# schema_Project.net
KiCad netlist of a schematic drawn in Altium Designer
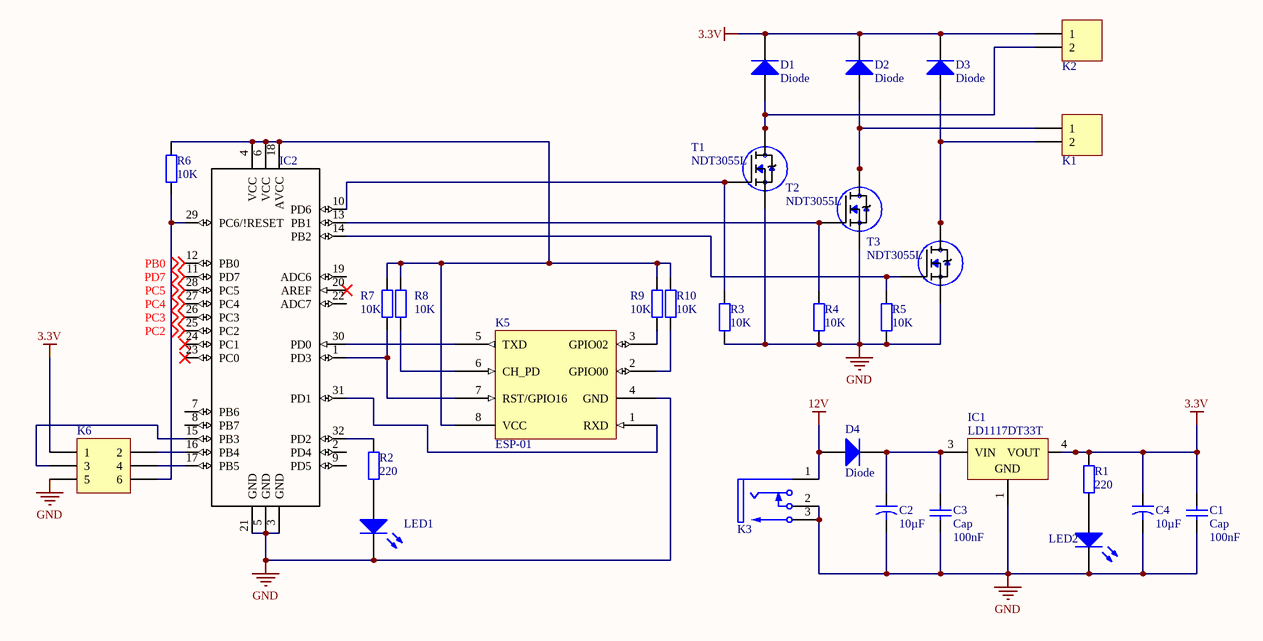
[diagram p0: schema_Project.SchDoc]

(export (version "E")
  (design (tool "Eeschema 10.0.6"))
  (components
    (comp (ref "C1")
      (value "Cap")
      (footprint "C13+R")
      (description "Capacitor")
      (fields (field (name "ALTIUM_VALUE") "100nF") (field (name "PUBLISHER") "Altium Limited"))
      (libsource (lib "Miscellaneous Devices") (part "Cap"))
    )
    (comp (ref "C2")
      (value "10µF")
      (footprint "C24")
      (description "Capacitor")
      (fields (field (name "Comment") "Cap2") (field (name "PUBLISHER") "Altium Limited"))
      (libsource (lib "Miscellaneous Devices") (part "Cap2"))
    )
    (comp (ref "C3")
      (value "Cap")
      (footprint "C13+R")
      (description "Capacitor")
      (fields (field (name "ALTIUM_VALUE") "100nF") (field (name "PUBLISHER") "Altium Limited"))
      (libsource (lib "Miscellaneous Devices") (part "Cap"))
    )
    (comp (ref "C4")
      (value "10µF")
      (footprint "C24")
      (description "Capacitor")
      (fields (field (name "Comment") "Cap2") (field (name "PUBLISHER") "Altium Limited"))
      (libsource (lib "Miscellaneous Devices") (part "Cap2"))
    )
    (comp (ref "D1")
      (value "Diode")
      (footprint "Diode")
      (description "Default Diode")
      (fields (field (name "PUBLISHER") "Altium Limited"))
      (libsource (lib "Miscellaneous Devices") (part "Diode"))
    )
    (comp (ref "D2")
      (value "Diode")
      (footprint "Diode")
      (description "Default Diode")
      (fields (field (name "PUBLISHER") "Altium Limited"))
      (libsource (lib "Miscellaneous Devices") (part "Diode"))
    )
    (comp (ref "D3")
      (value "Diode")
      (footprint "Diode")
      (description "Default Diode")
      (fields (field (name "PUBLISHER") "Altium Limited"))
      (libsource (lib "Miscellaneous Devices") (part "Diode"))
    )
    (comp (ref "D4")
      (value "Diode")
      (footprint "Diode")
      (description "Default Diode")
      (fields (field (name "PUBLISHER") "Altium Limited"))
      (libsource (lib "Miscellaneous Devices") (part "Diode"))
    )
    (comp (ref "ESP-01") (value "K5") (footprint "HDR2X4") (libsource (lib "ESP-01") (part "K5")))
    (comp (ref "IC1")
      (value "LD1117DT33T")
      (footprint "TO-252_N")
      (description "Fixed Low Drop Positive Voltage Regulator, 3.3V, 3-Pin DPAK, Tape and Reel")
      (libsource (lib "Altium Content Vault") (part "PM-REG-LD1117-SOT3"))
    )
    (comp (ref "IC2")
      (value "ATMEGA328P-AU")
      (footprint "*QFP80P900X900X120-32N")
      (libsource (lib "AT-MEGA") (part "Component_1"))
    )
    (comp (ref "K1")
      (value "K1")
      (footprint "K12")
      (description "Header, 2-Pin")
      (fields (field (name "PUBLISHER") "Altium Limited"))
      (libsource (lib "Miscellaneous Connectors") (part "Header 2"))
    )
    (comp (ref "K2")
      (value "K2")
      (footprint "K12")
      (description "Header, 2-Pin")
      (fields (field (name "PUBLISHER") "Altium Limited"))
      (libsource (lib "Miscellaneous Connectors") (part "Header 2"))
    )
    (comp (ref "K3")
      (value "K3")
      (footprint "SWITCH-RAPC712X-3_V")
      (description "Power Jack, 5 A, 3-Pin THD, RoHS, Bulk")
      (fields (field (name "MANUFACTURER") "Switchcraft"))
      (libsource (lib "Altium Content Vault") (part "SWITCH-RAPC712X-3"))
    )
    (comp (ref "K6")
      (value "Header 3X2")
      (footprint "HDR2X3")
      (description "Header, 3-Pin, Dual row")
      (fields (field (name "PUBLISHER") "Altium Limited"))
      (libsource (lib "Miscellaneous Connectors") (part "Header 3X2"))
    )
    (comp (ref "LED1")
      (value "LED1")
      (footprint "LED")
      (description "Typical RED GaAs LED")
      (fields (field (name "PUBLISHER") "Altium Limited"))
      (libsource (lib "Miscellaneous Devices") (part "LED1"))
    )
    (comp (ref "LED2")
      (value "LED2")
      (footprint "LED")
      (description "Typical RED, GREEN, YELLOW, AMBER GaAs LED")
      (fields (field (name "PUBLISHER") "Altium Limited"))
      (libsource (lib "Miscellaneous Devices") (part "LED2"))
    )
    (comp (ref "R1")
      (value "220")
      (footprint "C13+R")
      (description "Resistor")
      (fields (field (name "Comment") "Res2") (field (name "PUBLISHER") "Altium Limited"))
      (libsource (lib "Miscellaneous Devices") (part "Res2"))
    )
    (comp (ref "R2")
      (value "220")
      (footprint "C13+R")
      (description "Resistor")
      (fields (field (name "Comment") "Res2") (field (name "PUBLISHER") "Altium Limited"))
      (libsource (lib "Miscellaneous Devices") (part "Res2"))
    )
    (comp (ref "R3")
      (value "10K")
      (footprint "C13+R")
      (description "Resistor")
      (fields (field (name "Comment") "Res2") (field (name "PUBLISHER") "Altium Limited"))
      (libsource (lib "") (part "Res2_1"))
    )
    (comp (ref "R4")
      (value "10K")
      (footprint "C13+R")
      (description "Resistor")
      (fields (field (name "Comment") "Res2") (field (name "PUBLISHER") "Altium Limited"))
      (libsource (lib "Miscellaneous Devices") (part "Res2"))
    )
    (comp (ref "R5")
      (value "10K")
      (footprint "C13+R")
      (description "Resistor")
      (fields (field (name "Comment") "Res2") (field (name "PUBLISHER") "Altium Limited"))
      (libsource (lib "Miscellaneous Devices") (part "Res2"))
    )
    (comp (ref "R6")
      (value "10K")
      (footprint "C13+R")
      (description "Resistor")
      (fields (field (name "Comment") "Res2") (field (name "PUBLISHER") "Altium Limited"))
      (libsource (lib "Miscellaneous Devices") (part "Res2"))
    )
    (comp (ref "R7")
      (value "10K")
      (footprint "C13+R")
      (description "Resistor")
      (fields (field (name "Comment") "Res2") (field (name "PUBLISHER") "Altium Limited"))
      (libsource (lib "") (part "Res2_1"))
    )
    (comp (ref "R8")
      (value "10K")
      (footprint "C13+R")
      (description "Resistor")
      (fields (field (name "Comment") "Res2") (field (name "PUBLISHER") "Altium Limited"))
      (libsource (lib "Miscellaneous Devices") (part "Res2"))
    )
    (comp (ref "R9")
      (value "10K")
      (footprint "C13+R")
      (description "Resistor")
      (fields (field (name "Comment") "Res2") (field (name "PUBLISHER") "Altium Limited"))
      (libsource (lib "Miscellaneous Devices") (part "Res2"))
    )
    (comp (ref "R10")
      (value "10K")
      (footprint "C13+R")
      (description "Resistor")
      (fields (field (name "Comment") "Res2") (field (name "PUBLISHER") "Altium Limited"))
      (libsource (lib "Miscellaneous Devices") (part "Res2"))
    )
    (comp (ref "T1")
      (value "NDT3055L")
      (footprint "*SOT223-4")
      (libsource (lib "NDT3055L") (part "NDT3055L"))
    )
    (comp (ref "T2")
      (value "NDT3055L")
      (footprint "*SOT223-4")
      (libsource (lib "NDT3055L") (part "NDT3055L"))
    )
    (comp (ref "T3")
      (value "NDT3055L")
      (footprint "*SOT223-4")
      (libsource (lib "NDT3055L") (part "NDT3055L"))
    )
  )
  (nets
    (net (code "1") (name "3.3V") (class "Default")
      (node (ref "C1") (pin "2") (pinfunction "2_2") (pintype "passive"))
      (node (ref "C4") (pin "1") (pinfunction "1_1") (pintype "passive"))
      (node (ref "D1") (pin "K") (pinfunction "K_K") (pintype "passive"))
      (node (ref "D2") (pin "K") (pinfunction "K_K") (pintype "passive"))
      (node (ref "D3") (pin "K") (pinfunction "K_K") (pintype "passive"))
      (node (ref "IC1") (pin "4") (pinfunction "VOUT_4") (pintype "power_in"))
      (node (ref "K2") (pin "1") (pinfunction "1_1") (pintype "passive"))
      (node (ref "K6") (pin "1") (pinfunction "1_1") (pintype "passive"))
      (node (ref "R1") (pin "2") (pinfunction "2_2") (pintype "passive"))
    )
    (net (code "2") (name "12V") (class "Default")
      (node (ref "D4") (pin "A") (pinfunction "A_A") (pintype "passive"))
      (node (ref "K3") (pin "1") (pinfunction "1_1") (pintype "passive"))
    )
    (net (code "3") (name "GND") (class "Default")
      (node (ref "C1") (pin "1") (pinfunction "1_1") (pintype "passive"))
      (node (ref "C2") (pin "2") (pinfunction "2_2") (pintype "passive"))
      (node (ref "C3") (pin "1") (pinfunction "1_1") (pintype "passive"))
      (node (ref "C4") (pin "2") (pinfunction "2_2") (pintype "passive"))
      (node (ref "ESP-01") (pin "4") (pinfunction "GND_4") (pintype "passive"))
      (node (ref "IC1") (pin "1") (pinfunction "GND_1") (pintype "power_in"))
      (node (ref "IC2") (pin "21") (pinfunction "GND_21") (pintype "power_in"))
      (node (ref "IC2") (pin "3") (pinfunction "GND_3") (pintype "power_in"))
      (node (ref "IC2") (pin "5") (pinfunction "GND_5") (pintype "power_in"))
      (node (ref "K3") (pin "2") (pinfunction "2_2") (pintype "passive"))
      (node (ref "K3") (pin "3") (pinfunction "3_3") (pintype "passive"))
      (node (ref "K6") (pin "5") (pinfunction "5_5") (pintype "passive"))
      (node (ref "LED1") (pin "K") (pinfunction "K_K") (pintype "passive"))
      (node (ref "LED2") (pin "K") (pinfunction "K_K") (pintype "passive"))
      (node (ref "R3") (pin "2") (pinfunction "2_2") (pintype "passive"))
      (node (ref "R4") (pin "1") (pinfunction "1_1") (pintype "passive"))
      (node (ref "R5") (pin "1") (pinfunction "1_1") (pintype "passive"))
      (node (ref "T1") (pin "3") (pinfunction "S_3") (pintype "passive"))
      (node (ref "T2") (pin "3") (pinfunction "S_3") (pintype "passive"))
      (node (ref "T3") (pin "3") (pinfunction "S_3") (pintype "passive"))
    )
    (net (code "4") (name "Net-(D1-PadA)") (class "Default")
      (node (ref "D1") (pin "A") (pinfunction "A_A") (pintype "passive"))
      (node (ref "K2") (pin "2") (pinfunction "2_2") (pintype "passive"))
      (node (ref "T1") (pin "2") (pinfunction "D_2") (pintype "passive"))
      (node (ref "T1") (pin "4") (pinfunction "D_4") (pintype "passive"))
    )
    (net (code "5") (name "Net-(D2-PadA)") (class "Default")
      (node (ref "D2") (pin "A") (pinfunction "A_A") (pintype "passive"))
      (node (ref "K1") (pin "1") (pinfunction "1_1") (pintype "passive"))
      (node (ref "T2") (pin "2") (pinfunction "D_2") (pintype "passive"))
      (node (ref "T2") (pin "4") (pinfunction "D_4") (pintype "passive"))
    )
    (net (code "6") (name "Net-(D3-PadA)") (class "Default")
      (node (ref "D3") (pin "A") (pinfunction "A_A") (pintype "passive"))
      (node (ref "K1") (pin "2") (pinfunction "2_2") (pintype "passive"))
      (node (ref "T3") (pin "2") (pinfunction "D_2") (pintype "passive"))
      (node (ref "T3") (pin "4") (pinfunction "D_4") (pintype "passive"))
    )
    (net (code "7") (name "Net-(ESP-01-CH_PD)") (class "Default")
      (node (ref "ESP-01") (pin "6") (pinfunction "CH_PD_6") (pintype "input"))
      (node (ref "R8") (pin "1") (pinfunction "1_1") (pintype "passive"))
    )
    (net (code "8") (name "Net-(ESP-01-GPIO00)") (class "Default")
      (node (ref "ESP-01") (pin "2") (pinfunction "GPIO00_2") (pintype "bidirectional"))
      (node (ref "R10") (pin "1") (pinfunction "1_1") (pintype "passive"))
    )
    (net (code "9") (name "Net-(ESP-01-GPIO02)") (class "Default")
      (node (ref "ESP-01") (pin "3") (pinfunction "GPIO02_3") (pintype "bidirectional"))
      (node (ref "R9") (pin "1") (pinfunction "1_1") (pintype "passive"))
    )
    (net (code "10") (name "Net-(ESP-01-RST{slash}GPIO16)") (class "Default")
      (node (ref "ESP-01") (pin "7") (pinfunction "RST/GPIO16_7") (pintype "input"))
      (node (ref "IC2") (pin "1") (pinfunction "PD3_1") (pintype "bidirectional"))
      (node (ref "R7") (pin "2") (pinfunction "2_2") (pintype "passive"))
    )
    (net (code "11") (name "Net-(ESP-01-RXD)") (class "Default")
      (node (ref "ESP-01") (pin "1") (pinfunction "RXD_1") (pintype "input"))
      (node (ref "IC2") (pin "31") (pinfunction "PD1_31") (pintype "bidirectional"))
    )
    (net (code "12") (name "Net-(ESP-01-TXD)") (class "Default")
      (node (ref "ESP-01") (pin "5") (pinfunction "TXD_5") (pintype "output"))
      (node (ref "IC2") (pin "30") (pinfunction "PD0_30") (pintype "input"))
    )
    (net (code "13") (name "Net-(ESP-01-VCC)") (class "Default")
      (node (ref "ESP-01") (pin "8") (pinfunction "VCC_8") (pintype "passive"))
      (node (ref "IC2") (pin "18") (pinfunction "AVCC_18") (pintype "power_in"))
      (node (ref "IC2") (pin "4") (pinfunction "VCC_4") (pintype "power_in"))
      (node (ref "IC2") (pin "6") (pinfunction "VCC_6") (pintype "power_in"))
      (node (ref "R10") (pin "2") (pinfunction "2_2") (pintype "passive"))
      (node (ref "R6") (pin "2") (pinfunction "2_2") (pintype "passive"))
      (node (ref "R7") (pin "1") (pinfunction "1_1") (pintype "passive"))
      (node (ref "R8") (pin "2") (pinfunction "2_2") (pintype "passive"))
      (node (ref "R9") (pin "2") (pinfunction "2_2") (pintype "passive"))
    )
    (net (code "14") (name "Net-(IC1-VIN)") (class "Default")
      (node (ref "C2") (pin "1") (pinfunction "1_1") (pintype "passive"))
      (node (ref "C3") (pin "2") (pinfunction "2_2") (pintype "passive"))
      (node (ref "D4") (pin "K") (pinfunction "K_K") (pintype "passive"))
      (node (ref "IC1") (pin "3") (pinfunction "VIN_3") (pintype "power_in"))
    )
    (net (code "15") (name "Net-(IC2-PB1)") (class "Default")
      (node (ref "IC2") (pin "13") (pinfunction "PB1_13") (pintype "bidirectional"))
      (node (ref "R4") (pin "2") (pinfunction "2_2") (pintype "passive"))
      (node (ref "T2") (pin "1") (pinfunction "G_1") (pintype "passive"))
    )
    (net (code "16") (name "Net-(IC2-PB2)") (class "Default")
      (node (ref "IC2") (pin "14") (pinfunction "PB2_14") (pintype "bidirectional"))
      (node (ref "R5") (pin "2") (pinfunction "2_2") (pintype "passive"))
      (node (ref "T3") (pin "1") (pinfunction "G_1") (pintype "passive"))
    )
    (net (code "17") (name "Net-(IC2-PB3)") (class "Default")
      (node (ref "IC2") (pin "15") (pinfunction "PB3_15") (pintype "bidirectional"))
      (node (ref "K6") (pin "3") (pinfunction "3_3") (pintype "passive"))
    )
    (net (code "18") (name "Net-(IC2-PB4)") (class "Default")
      (node (ref "IC2") (pin "16") (pinfunction "PB4_16") (pintype "bidirectional"))
      (node (ref "K6") (pin "2") (pinfunction "2_2") (pintype "passive"))
    )
    (net (code "19") (name "Net-(IC2-PB5)") (class "Default")
      (node (ref "IC2") (pin "17") (pinfunction "PB5_17") (pintype "bidirectional"))
      (node (ref "K6") (pin "4") (pinfunction "4_4") (pintype "passive"))
    )
    (net (code "20") (name "Net-(IC2-PC6{slash}!RESET)") (class "Default")
      (node (ref "IC2") (pin "29") (pinfunction "PC6/!RESET_29") (pintype "bidirectional"))
      (node (ref "K6") (pin "6") (pinfunction "6_6") (pintype "passive"))
      (node (ref "R6") (pin "1") (pinfunction "1_1") (pintype "passive"))
    )
    (net (code "21") (name "Net-(IC2-PD2)") (class "Default")
      (node (ref "IC2") (pin "32") (pinfunction "PD2_32") (pintype "bidirectional"))
      (node (ref "R2") (pin "2") (pinfunction "2_2") (pintype "passive"))
    )
    (net (code "22") (name "Net-(IC2-PD6)") (class "Default")
      (node (ref "IC2") (pin "10") (pinfunction "PD6_10") (pintype "bidirectional"))
      (node (ref "R3") (pin "1") (pinfunction "1_1") (pintype "passive"))
      (node (ref "T1") (pin "1") (pinfunction "G_1") (pintype "passive"))
    )
    (net (code "23") (name "Net-(LED1-PadA)") (class "Default")
      (node (ref "LED1") (pin "A") (pinfunction "A_A") (pintype "passive"))
      (node (ref "R2") (pin "1") (pinfunction "1_1") (pintype "passive"))
    )
    (net (code "24") (name "Net-(LED2-PadA)") (class "Default")
      (node (ref "LED2") (pin "A") (pinfunction "A_A") (pintype "passive"))
      (node (ref "R1") (pin "1") (pinfunction "1_1") (pintype "passive"))
    )
    (net (code "25") (name "PB0") (class "Default")
      (node (ref "IC2") (pin "12") (pinfunction "PB0_12") (pintype "bidirectional"))
    )
    (net (code "26") (name "PC2") (class "Default")
      (node (ref "IC2") (pin "25") (pinfunction "PC2_25") (pintype "bidirectional"))
    )
    (net (code "27") (name "PC3") (class "Default")
      (node (ref "IC2") (pin "26") (pinfunction "PC3_26") (pintype "bidirectional"))
    )
    (net (code "28") (name "PC4") (class "Default")
      (node (ref "IC2") (pin "27") (pinfunction "PC4_27") (pintype "bidirectional"))
    )
    (net (code "29") (name "PC5") (class "Default")
      (node (ref "IC2") (pin "28") (pinfunction "PC5_28") (pintype "bidirectional"))
    )
    (net (code "30") (name "PD7") (class "Default")
      (node (ref "IC2") (pin "11") (pinfunction "PD7_11") (pintype "bidirectional"))
    )
    (net (code "31") (name "unconnected-(IC2-ADC6-Pad19)") (class "Default")
      (node (ref "IC2") (pin "19") (pinfunction "ADC6_19") (pintype "bidirectional"))
    )
    (net (code "32") (name "unconnected-(IC2-ADC7-Pad22)") (class "Default")
      (node (ref "IC2") (pin "22") (pinfunction "ADC7_22") (pintype "bidirectional"))
    )
    (net (code "33") (name "unconnected-(IC2-AREF-Pad20)") (class "Default")
      (node (ref "IC2") (pin "20") (pinfunction "AREF_20") (pintype "input+no_connect"))
    )
    (net (code "34") (name "unconnected-(IC2-PB6-Pad7)") (class "Default")
      (node (ref "IC2") (pin "7") (pinfunction "PB6_7") (pintype "bidirectional"))
    )
    (net (code "35") (name "unconnected-(IC2-PB7-Pad8)") (class "Default")
      (node (ref "IC2") (pin "8") (pinfunction "PB7_8") (pintype "bidirectional"))
    )
    (net (code "36") (name "unconnected-(IC2-PC0-Pad23)") (class "Default")
      (node (ref "IC2") (pin "23") (pinfunction "PC0_23") (pintype "bidirectional+no_connect"))
    )
    (net (code "37") (name "unconnected-(IC2-PC1-Pad24)") (class "Default")
      (node (ref "IC2") (pin "24") (pinfunction "PC1_24") (pintype "bidirectional+no_connect"))
    )
    (net (code "38") (name "unconnected-(IC2-PD4-Pad2)") (class "Default")
      (node (ref "IC2") (pin "2") (pinfunction "PD4_2") (pintype "bidirectional"))
    )
    (net (code "39") (name "unconnected-(IC2-PD5-Pad9)") (class "Default")
      (node (ref "IC2") (pin "9") (pinfunction "PD5_9") (pintype "bidirectional"))
    )
  )
)
